# Probe.net
KiCad netlist of a schematic drawn in Altium Designer
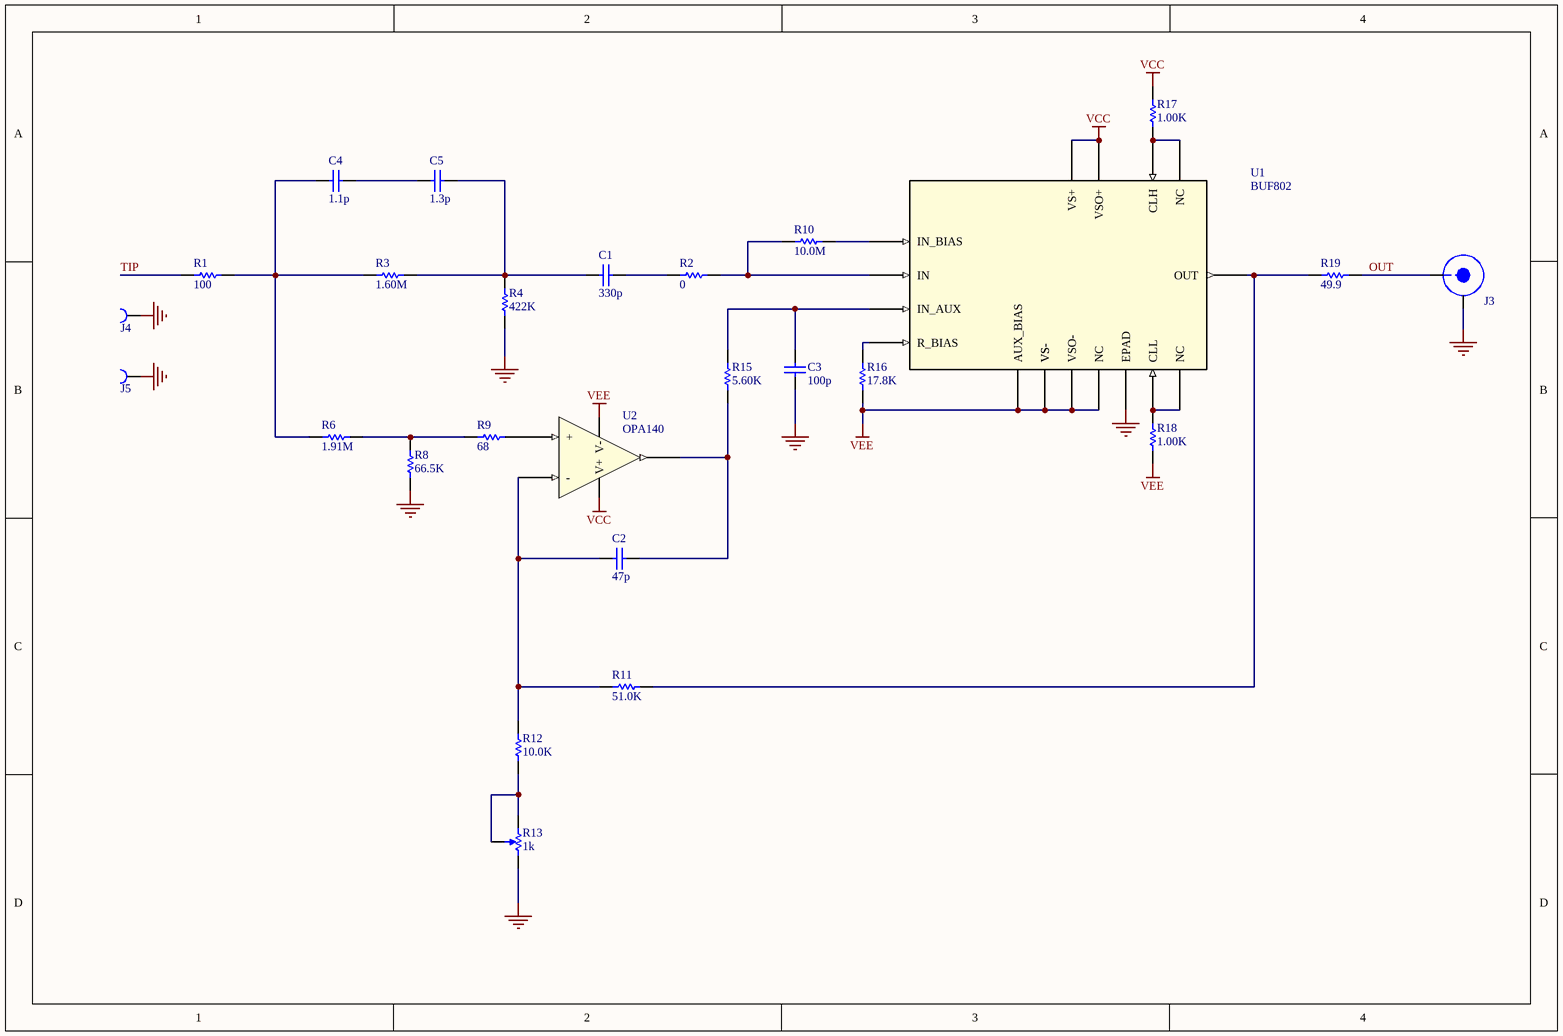
[diagram p0: Probe.SchDoc]

(export (version "E")
  (design (tool "Eeschema 10.0.6"))
  (components
    (comp (ref "C1")
      (value "330p")
      (footprint "CAPC0402(1005)50_M")
      (description "CAP CER 330PF±5% 50V C0G 0402")
      (fields
        (field (name "MANUFACTURER") "Murata")
        (field (name "MANUFACTURER PART NUMBER") "GRM1555C1H331JA01D")
      )
      (libsource (lib "Murata GRM 0402") (part "Capacitor_Generic"))
    )
    (comp (ref "C2")
      (value "47p")
      (footprint "CAPC0402(1005)50_M")
      (description "CAP CER 47PF±5% 50V C0G 0402")
      (fields
        (field (name "MANUFACTURER") "Samsung Electro-Mechanics")
        (field (name "MANUFACTURER PART NUMBER") "CL05C470JB5NNNC")
      )
      (libsource (lib "Samsung CAPC0402") (part "Capacitor_Generic"))
    )
    (comp (ref "C3")
      (value "100p")
      (footprint "CAPC0402(1005)50_M")
      (description "CAP CER 100PF±5% 50V C0G 0402")
      (fields
        (field (name "MANUFACTURER") "Samsung Electro-Mechanics")
        (field (name "MANUFACTURER PART NUMBER") "CL05C101JB5NNNC")
      )
      (libsource (lib "Samsung CAPC0402") (part "Capacitor_Generic"))
    )
    (comp (ref "C4")
      (value "1.1p")
      (footprint "CAPC0402(1005)50_M")
      (description "CAP CER 1.1PF±0.05PF 50V C0G/NP0 0402")
      (fields (field (name "PART NUMBER") "GJM1555C1H1R1WB01") (field (name "TOLERANCE") "±0.05pF"))
      (libsource (lib "Murata GJM 0402") (part "Capacitor_Generic"))
    )
    (comp (ref "C5")
      (value "1.3p")
      (footprint "CAPC0402(1005)50_M")
      (description "CAP CER 1.3PF±0.05PF 50V C0G/NP0 0402")
      (fields (field (name "PART NUMBER") "GJM1555C1H1R3WB01") (field (name "TOLERANCE") "±0.05pF"))
      (libsource (lib "Murata GJM 0402") (part "Capacitor_Generic"))
    )
    (comp (ref "J3")
      (value "BWSMA-KE-P001")
      (footprint "BATWIRELESS_BWSMA-KE-P001")
      (description "CONN SMA JACK STR 50OHM EDGE MNT")
      (fields (field (name "MANUFACTURER") "BAT WIRELESS"))
      (libsource (lib "Connectors") (part "901-10511-3"))
    )
    (comp (ref "J4")
      (value "0339-0-15-01-15-27-10-0")
      (footprint "MILL-MAX 0339")
      (description "CONN PIN RCPT")
      (fields (field (name "MANUFACTURER") "TE Connectivity"))
      (libsource (lib "Connectors") (part "0339-0-15-01-15-27-10-0"))
    )
    (comp (ref "J5")
      (value "0339-0-15-01-15-27-10-0")
      (footprint "MILL-MAX 0339")
      (description "CONN PIN RCPT")
      (fields (field (name "MANUFACTURER") "TE Connectivity"))
      (libsource (lib "Connectors") (part "0339-0-15-01-15-27-10-0"))
    )
    (comp (ref "R1")
      (value "100")
      (footprint "RESC0402(1005)_M")
      (description "RES 100 OHM 1% 1/16W 0402")
      (fields (field (name "PART NUMBER") "RESC0402-100R-1pct"))
      (libsource (lib "R0402 - 1pct") (part "Resistor_Generic"))
    )
    (comp (ref "R2")
      (value "0")
      (footprint "RESC0402(1005)_M")
      (description "RES 0 OHM JUMPER 0402")
      (fields (field (name "PART NUMBER") "R0402-0R0-JMP"))
      (libsource (lib "R0402 - 1pct") (part "Resistor_Generic"))
    )
    (comp (ref "R3")
      (value "1.60M")
      (footprint "RESC0402(1005)_M")
      (description "RES 1.60M OHM 1% 1/16W 0402")
      (fields (field (name "PART NUMBER") "RESC0402-1M60-1pct"))
      (libsource (lib "R0402 - 1pct") (part "Resistor_Generic"))
    )
    (comp (ref "R4")
      (value "422K")
      (footprint "RESC0402(1005)_M")
      (description "RES 422K OHM 1% 1/16W 0402")
      (fields (field (name "PART NUMBER") "RESC0402-422K-1pct"))
      (libsource (lib "R0402 - 1pct") (part "Resistor_Generic"))
    )
    (comp (ref "R6")
      (value "1.91M")
      (footprint "RESC0402(1005)_M")
      (description "RES 1.91M OHM 1% 1/16W 0402")
      (fields (field (name "PART NUMBER") "RESC0402-1M91-1pct"))
      (libsource (lib "R0402 - 1pct") (part "Resistor_Generic"))
    )
    (comp (ref "R8")
      (value "66.5K")
      (footprint "RESC0402(1005)_M")
      (description "RES 66.5K OHM 1% 1/16W 0402")
      (fields (field (name "PART NUMBER") "RESC0402-66K5-1pct"))
      (libsource (lib "R0402 - 1pct") (part "Resistor_Generic"))
    )
    (comp (ref "R9")
      (value "68")
      (footprint "RESC0402(1005)_M")
      (description "RES 68 OHM 1% 1/16W 0402")
      (fields (field (name "PART NUMBER") "RESC0402-68R0-1pct"))
      (libsource (lib "R0402 - 1pct") (part "Resistor_Generic"))
    )
    (comp (ref "R10")
      (value "10.0M")
      (footprint "RESC0402(1005)_M")
      (description "RES 10.0M OHM 1% 1/16W 0402")
      (fields (field (name "PART NUMBER") "RESC0402-10M0-1pct"))
      (libsource (lib "R0402 - 1pct") (part "Resistor_Generic"))
    )
    (comp (ref "R11")
      (value "51.0K")
      (footprint "RESC0402(1005)_M")
      (description "RES 51.0K OHM 1% 1/16W 0402")
      (fields (field (name "PART NUMBER") "RESC0402-51K0-1pct"))
      (libsource (lib "R0402 - 1pct") (part "Resistor_Generic"))
    )
    (comp (ref "R12")
      (value "10.0K")
      (footprint "RESC0402(1005)_M")
      (description "RES 10.0K OHM 1% 1/16W 0402")
      (fields (field (name "PART NUMBER") "RESC0402-10K0-1pct"))
      (libsource (lib "R0402 - 1pct") (part "Resistor_Generic"))
    )
    (comp (ref "R13")
      (value "1k")
      (footprint "PVG3A")
      (description "TRIMMER 1K OHM 0.25W J LEAD TOP")
      (fields
        (field (name "MANUFACTURER") "Bourns")
        (field (name "MANUFACTURER PART NUMBER") "PVG3A102C01R00")
      )
      (libsource (lib "Trimpots") (part "PVG3A102C01R00"))
    )
    (comp (ref "R15")
      (value "5.60K")
      (footprint "RESC0402(1005)_M")
      (description "RES 5.60K OHM 1% 1/16W 0402")
      (fields (field (name "PART NUMBER") "RESC0402-5K60-1pct"))
      (libsource (lib "R0402 - 1pct") (part "Resistor_Generic"))
    )
    (comp (ref "R16")
      (value "17.8K")
      (footprint "RESC0402(1005)_M")
      (description "RES 17.8K OHM 1% 1/16W 0402")
      (fields (field (name "PART NUMBER") "RESC0402-17K8-1pct"))
      (libsource (lib "R0402 - 1pct") (part "Resistor_Generic"))
    )
    (comp (ref "R17")
      (value "1.00K")
      (footprint "RESC0402(1005)_M")
      (description "RES 1.00K OHM 1% 1/16W 0402")
      (fields (field (name "PART NUMBER") "RESC0402-1K00-1pct"))
      (libsource (lib "R0402 - 1pct") (part "Resistor_Generic"))
    )
    (comp (ref "R18")
      (value "1.00K")
      (footprint "RESC0402(1005)_M")
      (description "RES 1.00K OHM 1% 1/16W 0402")
      (fields (field (name "PART NUMBER") "RESC0402-1K00-1pct"))
      (libsource (lib "R0402 - 1pct") (part "Resistor_Generic"))
    )
    (comp (ref "R19")
      (value "49.9")
      (footprint "RESC0402(1005)_M")
      (description "RES 49.9 OHM 1% 1/16W 0402")
      (fields (field (name "PART NUMBER") "RESC0402-49R9-1pct"))
      (libsource (lib "R0402 - 1pct") (part "Resistor_Generic"))
    )
    (comp (ref "U1")
      (value "BUF802")
      (footprint "VQFN16_RGT_TEX- OSHPARK")
      (description "WIDE-BANDWIDTH JFET BUFFER")
      (fields
        (field (name "MANUFACTURER") "Texas Instruments")
        (field (name "MANUFACTURER PART NUMBER") "BUF802IRGTR")
      )
      (libsource (lib "IC") (part "BUF802IRGTR"))
    )
    (comp (ref "U2")
      (value "OPA140")
      (footprint "SOIC-8")
      (description "IC OPAMP JFET 1 CIRCUIT 8SOIC")
      (fields
        (field (name "MANUFACTURER") "Texas Instruments")
        (field (name "MANUFACTURER PART NUMBER") "OPA140AIDR")
      )
      (libsource (lib "IC") (part "OPA140AIDR"))
    )
  )
  (nets
    (net (code "1") (name "/OUT") (class "Default")
      (node (ref "J3") (pin "1") (pinfunction "1_1") (pintype "passive"))
      (node (ref "R19") (pin "2") (pinfunction "2_2") (pintype "passive"))
    )
    (net (code "2") (name "/TIP") (class "Default")
      (node (ref "R1") (pin "1") (pinfunction "1_1") (pintype "passive"))
    )
    (net (code "3") (name "GND") (class "Default")
      (node (ref "C3") (pin "2") (pinfunction "2_2") (pintype "passive"))
      (node (ref "J3") (pin "2") (pinfunction "2_2") (pintype "passive"))
      (node (ref "J4") (pin "1") (pinfunction "1_1") (pintype "passive"))
      (node (ref "J5") (pin "1") (pinfunction "1_1") (pintype "passive"))
      (node (ref "R13") (pin "3") (pinfunction "3_3") (pintype "passive"))
      (node (ref "R4") (pin "2") (pinfunction "2_2") (pintype "passive"))
      (node (ref "R8") (pin "2") (pinfunction "2_2") (pintype "passive"))
      (node (ref "U1") (pin "17") (pinfunction "EPAD_17") (pintype "passive"))
    )
    (net (code "4") (name "Net-(C1-Pad1)") (class "Default")
      (node (ref "C1") (pin "1") (pinfunction "1_1") (pintype "passive"))
      (node (ref "C5") (pin "2") (pinfunction "2_2") (pintype "passive"))
      (node (ref "R3") (pin "2") (pinfunction "2_2") (pintype "passive"))
      (node (ref "R4") (pin "1") (pinfunction "1_1") (pintype "passive"))
    )
    (net (code "5") (name "Net-(C1-Pad2)") (class "Default")
      (node (ref "C1") (pin "2") (pinfunction "2_2") (pintype "passive"))
      (node (ref "R2") (pin "1") (pinfunction "1_1") (pintype "passive"))
    )
    (net (code "6") (name "Net-(C4-Pad1)") (class "Default")
      (node (ref "C4") (pin "1") (pinfunction "1_1") (pintype "passive"))
      (node (ref "R1") (pin "2") (pinfunction "2_2") (pintype "passive"))
      (node (ref "R3") (pin "1") (pinfunction "1_1") (pintype "passive"))
      (node (ref "R6") (pin "1") (pinfunction "1_1") (pintype "passive"))
    )
    (net (code "7") (name "Net-(C4-Pad2)") (class "Default")
      (node (ref "C4") (pin "2") (pinfunction "2_2") (pintype "passive"))
      (node (ref "C5") (pin "1") (pinfunction "1_1") (pintype "passive"))
    )
    (net (code "8") (name "Net-(R6-Pad2)") (class "Default")
      (node (ref "R6") (pin "2") (pinfunction "2_2") (pintype "passive"))
      (node (ref "R8") (pin "1") (pinfunction "1_1") (pintype "passive"))
      (node (ref "R9") (pin "1") (pinfunction "1_1") (pintype "passive"))
    )
    (net (code "9") (name "Net-(R12-Pad2)") (class "Default")
      (node (ref "R12") (pin "2") (pinfunction "2_2") (pintype "passive"))
      (node (ref "R13") (pin "1") (pinfunction "1_1") (pintype "passive"))
      (node (ref "R13") (pin "2") (pinfunction "2_2") (pintype "passive"))
    )
    (net (code "10") (name "Net-(U1-CLH)") (class "Default")
      (node (ref "R17") (pin "1") (pinfunction "1_1") (pintype "passive"))
      (node (ref "U1") (pin "15") (pinfunction "CLH_15") (pintype "input"))
      (node (ref "U1") (pin "16") (pinfunction "NC_16") (pintype "passive"))
    )
    (net (code "11") (name "Net-(U1-CLL)") (class "Default")
      (node (ref "R18") (pin "1") (pinfunction "1_1") (pintype "passive"))
      (node (ref "U1") (pin "13") (pinfunction "NC_13") (pintype "passive"))
      (node (ref "U1") (pin "14") (pinfunction "CLL_14") (pintype "input"))
    )
    (net (code "12") (name "Net-(U1-IN)") (class "Default")
      (node (ref "R10") (pin "1") (pinfunction "1_1") (pintype "passive"))
      (node (ref "R2") (pin "2") (pinfunction "2_2") (pintype "passive"))
      (node (ref "U1") (pin "2") (pinfunction "IN_2") (pintype "input"))
    )
    (net (code "13") (name "Net-(U1-IN_AUX)") (class "Default")
      (node (ref "C3") (pin "1") (pinfunction "1_1") (pintype "passive"))
      (node (ref "R15") (pin "1") (pinfunction "1_1") (pintype "passive"))
      (node (ref "U1") (pin "4") (pinfunction "IN_AUX_4") (pintype "input"))
    )
    (net (code "14") (name "Net-(U1-IN_BIAS)") (class "Default")
      (node (ref "R10") (pin "2") (pinfunction "2_2") (pintype "passive"))
      (node (ref "U1") (pin "3") (pinfunction "IN_BIAS_3") (pintype "input"))
    )
    (net (code "15") (name "Net-(U1-OUT)") (class "Default")
      (node (ref "R11") (pin "2") (pinfunction "2_2") (pintype "passive"))
      (node (ref "R19") (pin "1") (pinfunction "1_1") (pintype "passive"))
      (node (ref "U1") (pin "11") (pinfunction "OUT_11") (pintype "output"))
    )
    (net (code "16") (name "Net-(U1-R_BIAS)") (class "Default")
      (node (ref "R16") (pin "1") (pinfunction "1_1") (pintype "passive"))
      (node (ref "U1") (pin "7") (pinfunction "R_BIAS_7") (pintype "input"))
    )
    (net (code "17") (name "Net-(U2-+)") (class "Default")
      (node (ref "R9") (pin "2") (pinfunction "2_2") (pintype "passive"))
      (node (ref "U2") (pin "3") (pinfunction "+_3") (pintype "input"))
    )
    (net (code "18") (name "Net-(U2--)") (class "Default")
      (node (ref "C2") (pin "1") (pinfunction "1_1") (pintype "passive"))
      (node (ref "R11") (pin "1") (pinfunction "1_1") (pintype "passive"))
      (node (ref "R12") (pin "1") (pinfunction "1_1") (pintype "passive"))
      (node (ref "U2") (pin "2") (pinfunction "-_2") (pintype "input"))
    )
    (net (code "19") (name "Net-(U2-OUT)") (class "Default")
      (node (ref "C2") (pin "2") (pinfunction "2_2") (pintype "passive"))
      (node (ref "R15") (pin "2") (pinfunction "2_2") (pintype "passive"))
      (node (ref "U2") (pin "6") (pinfunction "OUT_6") (pintype "output"))
    )
    (net (code "20") (name "VCC") (class "Default")
      (node (ref "R17") (pin "2") (pinfunction "2_2") (pintype "passive"))
      (node (ref "U1") (pin "1") (pinfunction "VS+_1") (pintype "power_in"))
      (node (ref "U1") (pin "12") (pinfunction "VSO+_12") (pintype "power_in"))
      (node (ref "U2") (pin "7") (pinfunction "V+_7") (pintype "power_in"))
    )
    (net (code "21") (name "VEE") (class "Default")
      (node (ref "R16") (pin "2") (pinfunction "2_2") (pintype "passive"))
      (node (ref "R18") (pin "2") (pinfunction "2_2") (pintype "passive"))
      (node (ref "U1") (pin "10") (pinfunction "VSO-_10") (pintype "power_in"))
      (node (ref "U1") (pin "5") (pinfunction "VS-_5") (pintype "power_in"))
      (node (ref "U1") (pin "6") (pinfunction "AUX_BIAS_6") (pintype "power_in"))
      (node (ref "U1") (pin "8") (pinfunction "VS-_8") (pintype "power_in"))
      (node (ref "U1") (pin "9") (pinfunction "NC_9") (pintype "passive"))
      (node (ref "U2") (pin "4") (pinfunction "V-_4") (pintype "power_in"))
    )
  )
)
